# ProDocument___2024-02-25.net
KiCad netlist of a schematic drawn in EasyEDA Pro
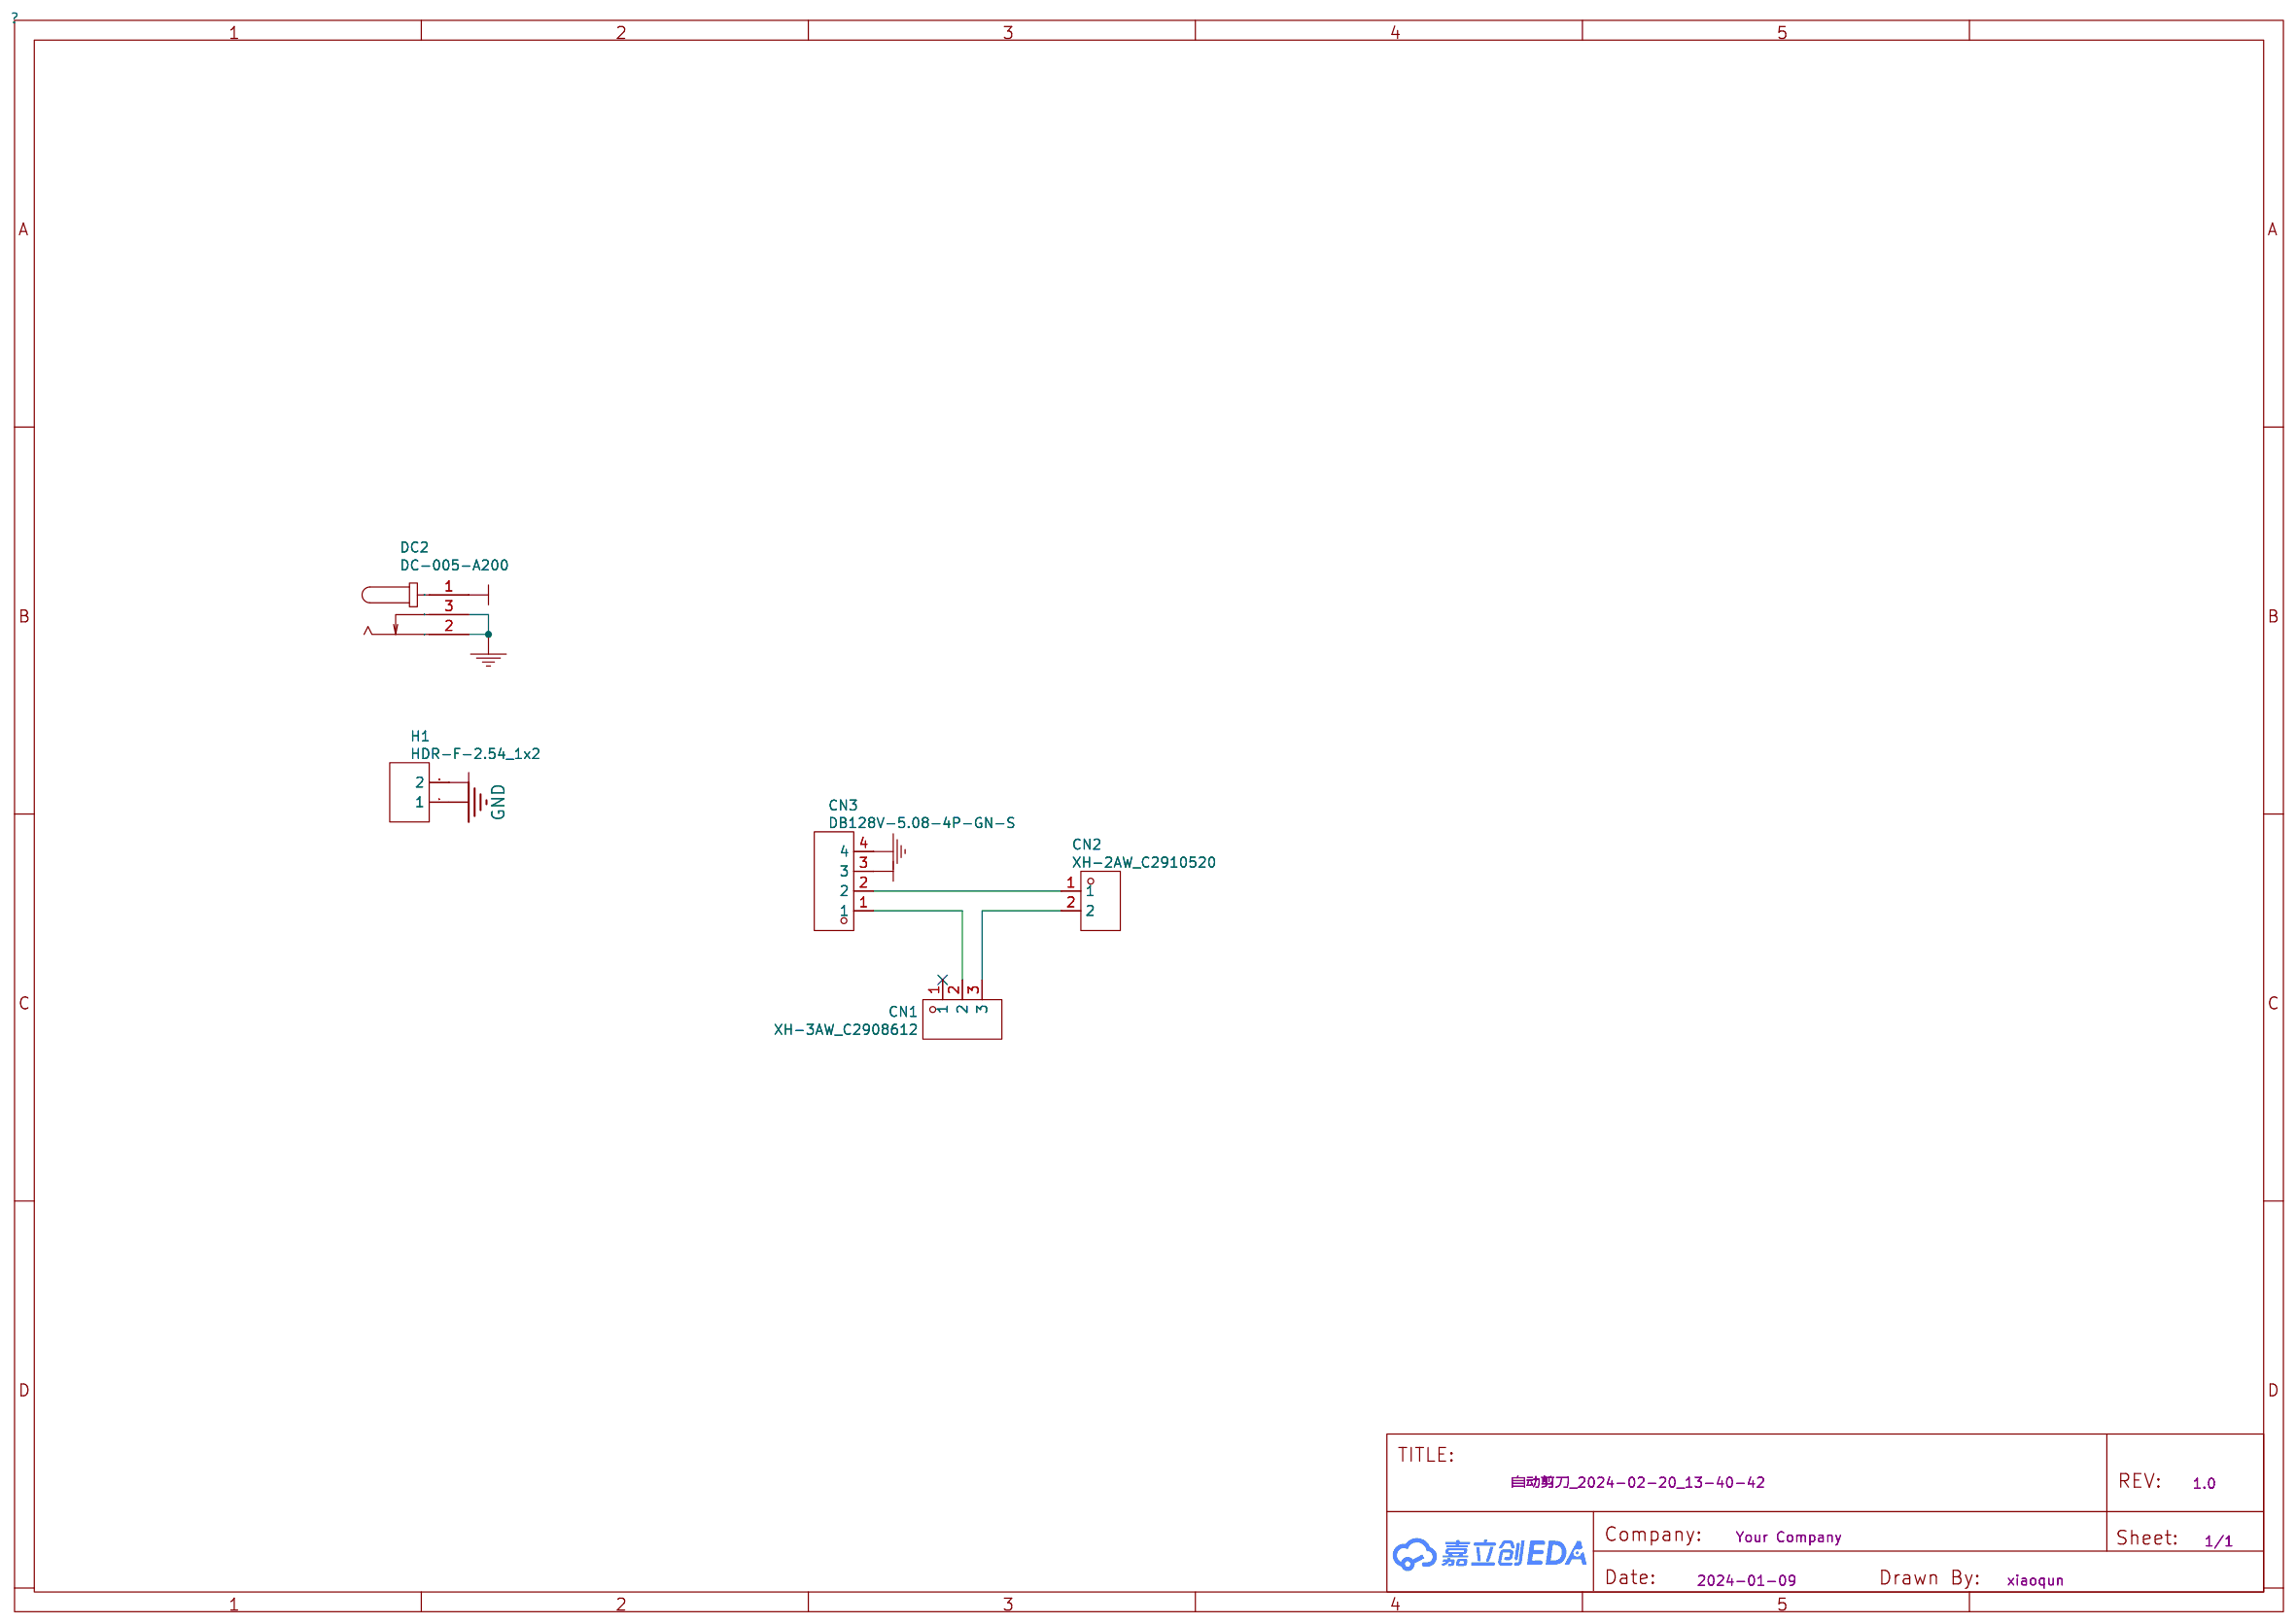
[diagram p0: schematic sheet]

(export (version "E")
  (design (tool "Eeschema 10.0.6"))
  (components
    (comp (ref "CN1")
      (value "XH-3AW_C2908612")
      (footprint "easyedapro:CONN-TH_3P-P2.54_HCTL_XH-3AW")
      (fields (field (name "Manufacturer Part") "XH-3AW") (field (name "Manufacturer") "HCTL(华灿天禄)"))
      (libsource (lib "easyedapro") (part "XH-3AW_C2908612"))
    )
    (comp (ref "CN2")
      (value "XH-2AW_C2910520")
      (footprint "easyedapro:CONN-TH_2P-P2.50_XH-2AW")
      (fields (field (name "Manufacturer Part") "XH-2AW") (field (name "Manufacturer") "韩国韩荣"))
      (libsource (lib "easyedapro") (part "XH-2AW_C2910520"))
    )
    (comp (ref "CN3")
      (value "DB128V-5.08-4P-GN-S")
      (footprint "easyedapro:CONN-TH_4P-P5.08_DIBO_DB128V-5.08")
      (fields (field (name "Manufacturer") "DORABO(地博电气)"))
      (libsource (lib "easyedapro") (part "DB128V-5.08-4P-GN-S"))
    )
    (comp (ref "DC2")
      (value "DC-005-A200")
      (footprint "easyedapro:DC-IN-TH_DC-005-A200")
      (fields (field (name "Manufacturer") "XUNPU(讯普)"))
      (libsource (lib "easyedapro") (part "DC-005-A200"))
    )
    (comp (ref "H1")
      (value "HDR-F-2.54_1x2")
      (footprint "easyedapro:HDR-F-2.54_1X2")
      (libsource (lib "easyedapro") (part "HDR-F-2.54_1x2"))
    )
  )
  (nets
    (net (code "1") (name "GND") (class "Default")
      (node (ref "CN3") (pin "4") (pinfunction "4_4") (pintype "unspecified"))
      (node (ref "DC2") (pin "2") (pinfunction "2_2") (pintype "unspecified"))
      (node (ref "DC2") (pin "3") (pinfunction "3_3") (pintype "unspecified"))
      (node (ref "H1") (pin "1") (pinfunction "1_1") (pintype "input"))
    )
    (net (code "2") (name "Net-(CN1-Pad2)") (class "Default")
      (node (ref "CN1") (pin "2") (pinfunction "2_2") (pintype "unspecified"))
      (node (ref "CN3") (pin "1") (pinfunction "1_1") (pintype "unspecified"))
    )
    (net (code "3") (name "Net-(CN1-Pad3)") (class "Default")
      (node (ref "CN1") (pin "3") (pinfunction "3_3") (pintype "unspecified"))
      (node (ref "CN2") (pin "2") (pinfunction "2_2") (pintype "unspecified"))
    )
    (net (code "4") (name "Net-(CN2-Pad1)") (class "Default")
      (node (ref "CN2") (pin "1") (pinfunction "1_1") (pintype "unspecified"))
      (node (ref "CN3") (pin "2") (pinfunction "2_2") (pintype "unspecified"))
    )
    (net (code "5") (name "VCC") (class "Default")
      (node (ref "CN3") (pin "3") (pinfunction "3_3") (pintype "unspecified"))
      (node (ref "DC2") (pin "1") (pinfunction "1_1") (pintype "unspecified"))
      (node (ref "H1") (pin "2") (pinfunction "2_2") (pintype "input"))
    )
    (net (code "6") (name "unconnected-(CN1-Pad1)") (class "Default")
      (node (ref "CN1") (pin "1") (pinfunction "1_1") (pintype "unspecified+no_connect"))
    )
  )
)
